# Enviro.net
KiCad netlist of a schematic drawn in EAGLE
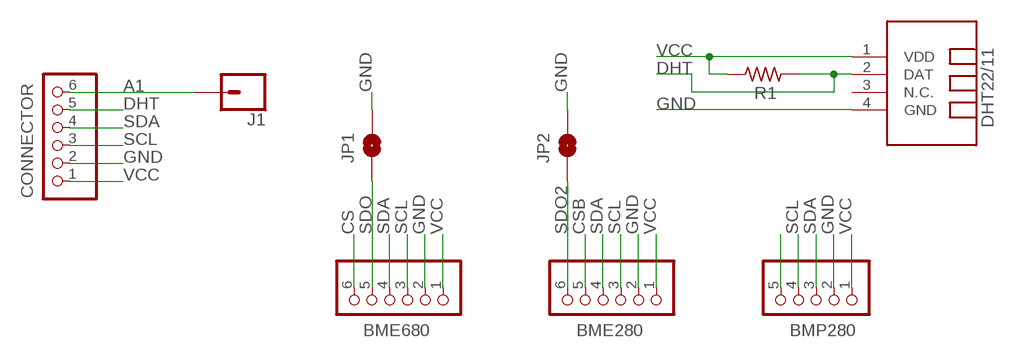
[diagram p0: schematic, sheet 1]

(export (version "E")
  (design (tool "Eeschema 10.0.6"))
  (components
    (comp (ref "BME280")
      (value "PINHD-1X6")
      (footprint "eagle-import:1X06")
      (libsource (lib "eagle-import") (part "PINHD-1X6"))
    )
    (comp (ref "BME680")
      (value "PINHD-1X6")
      (footprint "eagle-import:1X06")
      (libsource (lib "eagle-import") (part "PINHD-1X6"))
    )
    (comp (ref "BMP280")
      (value "PINHD-1X5")
      (footprint "eagle-import:1X05")
      (libsource (lib "eagle-import") (part "PINHD-1X5"))
    )
    (comp (ref "CONNECTOR")
      (value "PINHD-1X6")
      (footprint "eagle-import:1X06")
      (libsource (lib "eagle-import") (part "PINHD-1X6"))
    )
    (comp (ref "J1")
      (value "CONN_01PTH_LONGPAD")
      (footprint "eagle-import:1X01_LONGPAD")
      (libsource (lib "eagle-import") (part "CONN_01PTH_LONGPAD"))
    )
    (comp (ref "JP1")
      (value "JUMPER-SMT_2_NO_SILK")
      (footprint "eagle-import:SMT-JUMPER_2_NO_SILK")
      (libsource (lib "eagle-import") (part "JUMPER-SMT_2_NO_SILK"))
    )
    (comp (ref "JP2")
      (value "JUMPER-SMT_2_NO_SILK")
      (footprint "eagle-import:SMT-JUMPER_2_NO_SILK")
      (libsource (lib "eagle-import") (part "JUMPER-SMT_2_NO_SILK"))
    )
    (comp (ref "R1")
      (value "R-US_R1206")
      (footprint "eagle-import:R1206")
      (libsource (lib "eagle-import") (part "R-US_R1206"))
    )
    (comp (ref "U$1")
      (value "DHT22/11")
      (footprint "eagle-import:TEMP-HUM-SENSOR-DHT22")
      (libsource (lib "eagle-import") (part "TEMP-HUM-SENSOR-DHT22"))
    )
  )
  (nets
    (net (code "1") (name "/A1") (class "Default")
      (node (ref "CONNECTOR") (pin "6") (pinfunction "6_6") (pintype "passive"))
      (node (ref "J1") (pin "1") (pinfunction "1_1") (pintype "passive"))
    )
    (net (code "2") (name "/CS") (class "Default")
      (node (ref "BME680") (pin "6") (pinfunction "6_6") (pintype "passive"))
    )
    (net (code "3") (name "/CSB") (class "Default")
      (node (ref "BME280") (pin "5") (pinfunction "5_5") (pintype "passive"))
    )
    (net (code "4") (name "/DHT") (class "Default")
      (node (ref "CONNECTOR") (pin "5") (pinfunction "5_5") (pintype "passive"))
      (node (ref "R1") (pin "2") (pinfunction "2_2") (pintype "passive"))
      (node (ref "U$1") (pin "2") (pinfunction "DAT_2") (pintype "bidirectional"))
    )
    (net (code "5") (name "/GND") (class "Default")
      (node (ref "BME280") (pin "2") (pinfunction "2_2") (pintype "passive"))
      (node (ref "BME680") (pin "2") (pinfunction "2_2") (pintype "passive"))
      (node (ref "BMP280") (pin "2") (pinfunction "2_2") (pintype "passive"))
      (node (ref "CONNECTOR") (pin "2") (pinfunction "2_2") (pintype "passive"))
      (node (ref "JP1") (pin "2") (pinfunction "2_2") (pintype "passive"))
      (node (ref "JP2") (pin "2") (pinfunction "2_2") (pintype "passive"))
      (node (ref "U$1") (pin "4") (pinfunction "GND_4") (pintype "power_in"))
    )
    (net (code "6") (name "/SCL") (class "Default")
      (node (ref "BME280") (pin "3") (pinfunction "3_3") (pintype "passive"))
      (node (ref "BME680") (pin "3") (pinfunction "3_3") (pintype "passive"))
      (node (ref "BMP280") (pin "4") (pinfunction "4_4") (pintype "passive"))
      (node (ref "CONNECTOR") (pin "3") (pinfunction "3_3") (pintype "passive"))
    )
    (net (code "7") (name "/SDA") (class "Default")
      (node (ref "BME280") (pin "4") (pinfunction "4_4") (pintype "passive"))
      (node (ref "BME680") (pin "4") (pinfunction "4_4") (pintype "passive"))
      (node (ref "BMP280") (pin "3") (pinfunction "3_3") (pintype "passive"))
      (node (ref "CONNECTOR") (pin "4") (pinfunction "4_4") (pintype "passive"))
    )
    (net (code "8") (name "/SDO") (class "Default")
      (node (ref "BME680") (pin "5") (pinfunction "5_5") (pintype "passive"))
      (node (ref "JP1") (pin "1") (pinfunction "1_1") (pintype "passive"))
    )
    (net (code "9") (name "/SDO2") (class "Default")
      (node (ref "BME280") (pin "6") (pinfunction "6_6") (pintype "passive"))
      (node (ref "JP2") (pin "1") (pinfunction "1_1") (pintype "passive"))
    )
    (net (code "10") (name "/VCC") (class "Default")
      (node (ref "BME280") (pin "1") (pinfunction "1_1") (pintype "passive"))
      (node (ref "BME680") (pin "1") (pinfunction "1_1") (pintype "passive"))
      (node (ref "BMP280") (pin "1") (pinfunction "1_1") (pintype "passive"))
      (node (ref "CONNECTOR") (pin "1") (pinfunction "1_1") (pintype "passive"))
      (node (ref "R1") (pin "1") (pinfunction "1_1") (pintype "passive"))
      (node (ref "U$1") (pin "1") (pinfunction "VDD_1") (pintype "power_in"))
    )
    (net (code "11") (name "unconnected-(BMP280-Pad5)") (class "Default")
      (node (ref "BMP280") (pin "5") (pinfunction "5_5") (pintype "passive"))
    )
    (net (code "12") (name "unconnected-(U$1-N.C.-Pad3)") (class "Default")
      (node (ref "U$1") (pin "3") (pinfunction "N.C._3") (pintype "passive"))
    )
  )
)
